# stm8s003f3.net
KiCad netlist of a schematic drawn in Altium Designer
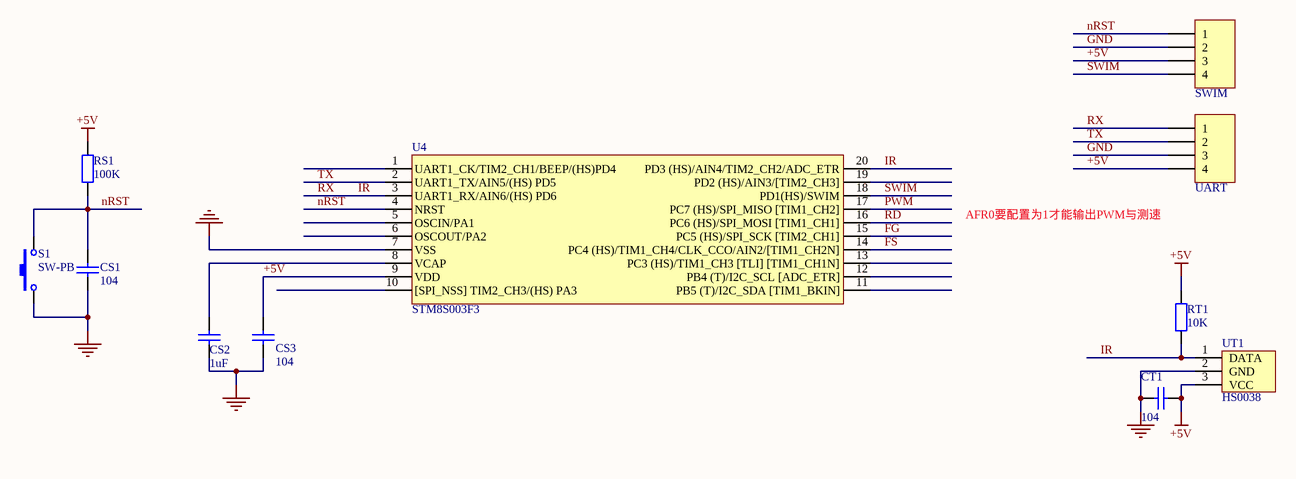
[diagram p0: stm8s003f3.SchDoc]

(export (version "E")
  (design (tool "Eeschema 10.0.6"))
  (components
    (comp (ref "CS1")
      (value "104")
      (footprint "CAPC1608N")
      (description "Capacitor")
      (fields (field (name "Comment") "Cap1") (field (name "PUBLISHER") "Altium Limited"))
      (libsource (lib "Peace的集成库") (part "Cap1"))
    )
    (comp (ref "CS2")
      (value "1uF")
      (footprint "CAPC1608N")
      (description "Capacitor")
      (fields (field (name "Comment") "Cap1") (field (name "PUBLISHER") "Altium Limited"))
      (libsource (lib "Peace的集成库") (part "Cap1"))
    )
    (comp (ref "CS3")
      (value "104")
      (footprint "CAPC1608N")
      (description "Capacitor")
      (fields (field (name "Comment") "Cap1") (field (name "PUBLISHER") "Altium Limited"))
      (libsource (lib "Peace的集成库") (part "Cap1"))
    )
    (comp (ref "CT1")
      (value "104")
      (footprint "CAPC1608N")
      (description "Capacitor")
      (fields (field (name "Comment") "Cap1") (field (name "PUBLISHER") "Altium Limited"))
      (libsource (lib "Peace的集成库") (part "Cap1"))
    )
    (comp (ref "RS1")
      (value "100K")
      (footprint "RESC1608N")
      (description "Resistor")
      (fields (field (name "Comment") "Res1") (field (name "PUBLISHER") "Altium Limited"))
      (libsource (lib "Peace的集成库") (part "Res1"))
    )
    (comp (ref "RT1")
      (value "10K")
      (footprint "RESC1608N")
      (description "Resistor")
      (fields (field (name "Comment") "Res1") (field (name "PUBLISHER") "Altium Limited"))
      (libsource (lib "") (part "Res1_1"))
    )
    (comp (ref "S1")
      (value "SW-PB")
      (footprint "SW-3x6")
      (description "Switch")
      (fields (field (name "PUBLISHER") "Altium Limited"))
      (libsource (lib "Peace的集成库") (part "SW-PB"))
    )
    (comp (ref "SWIM")
      (value "Header 4")
      (footprint "HDR1X4")
      (description "Header, 4-Pin")
      (fields (field (name "PUBLISHER") "Altium Limited"))
      (libsource (lib "Peace的集成库") (part "Header 4"))
    )
    (comp (ref "U4")
      (value "STM8S003F3")
      (footprint "TSSOP20_N")
      (libsource (lib "原理图库") (part "STM8S003F3"))
    )
    (comp (ref "UART")
      (value "Header 4")
      (footprint "HDR1X4")
      (description "Header, 4-Pin")
      (fields (field (name "PUBLISHER") "Altium Limited"))
      (libsource (lib "Peace的集成库") (part "Header 4"))
    )
    (comp (ref "UT1") (value "HS0038") (footprint "HS0038") (libsource (lib "原理图库") (part "HS0038")))
  )
  (nets
    (net (code "1") (name "+5V") (class "Default")
      (node (ref "CS3") (pin "2") (pinfunction "2_2") (pintype "passive"))
      (node (ref "CT1") (pin "1") (pinfunction "1_1") (pintype "passive"))
      (node (ref "RS1") (pin "2") (pinfunction "2_2") (pintype "passive"))
      (node (ref "RT1") (pin "1") (pinfunction "1_1") (pintype "passive"))
      (node (ref "SWIM") (pin "3") (pinfunction "3_3") (pintype "passive"))
      (node (ref "U4") (pin "9") (pinfunction "VDD_9") (pintype "passive"))
      (node (ref "UART") (pin "4") (pinfunction "4_4") (pintype "passive"))
      (node (ref "UT1") (pin "3") (pinfunction "VCC_3") (pintype "passive"))
    )
    (net (code "2") (name "/FG") (class "Default")
      (node (ref "U4") (pin "15") (pinfunction "PC5_(HS)/SPI_SCK_[TIM2_CH1]_15") (pintype "passive"))
    )
    (net (code "3") (name "/FS") (class "Default")
      (node (ref "U4") (pin "14") (pinfunction "PC4_(HS)/TIM1_CH4/CLK_CCO/AIN2/[TIM1_CH2N]_14") (pintype "passive"))
    )
    (net (code "4") (name "/IR") (class "Default")
      (node (ref "RT1") (pin "2") (pinfunction "2_2") (pintype "passive"))
      (node (ref "U4") (pin "20") (pinfunction "PD3_(HS)/AIN4/TIM2_CH2/ADC_ETR_20") (pintype "passive"))
      (node (ref "U4") (pin "3") (pinfunction "UART1_RX/AIN6/(HS)_PD6_3") (pintype "passive"))
      (node (ref "UART") (pin "1") (pinfunction "1_1") (pintype "passive"))
      (node (ref "UT1") (pin "1") (pinfunction "DATA_1") (pintype "passive"))
    )
    (net (code "5") (name "/PWM") (class "Default")
      (node (ref "U4") (pin "17") (pinfunction "PC7_(HS)/SPI_MISO_[TIM1_CH2]_17") (pintype "passive"))
    )
    (net (code "6") (name "/RD") (class "Default")
      (node (ref "U4") (pin "16") (pinfunction "PC6_(HS)/SPI_MOSI_[TIM1_CH1]_16") (pintype "passive"))
    )
    (net (code "7") (name "/SWIM") (class "Default")
      (node (ref "SWIM") (pin "4") (pinfunction "4_4") (pintype "passive"))
      (node (ref "U4") (pin "18") (pinfunction "PD1(HS)/SWIM_18") (pintype "passive"))
    )
    (net (code "8") (name "/TX") (class "Default")
      (node (ref "U4") (pin "2") (pinfunction "UART1_TX/AIN5/(HS)_PD5_2") (pintype "passive"))
      (node (ref "UART") (pin "2") (pinfunction "2_2") (pintype "passive"))
    )
    (net (code "9") (name "/nRST") (class "Default")
      (node (ref "CS1") (pin "2") (pinfunction "2_2") (pintype "passive"))
      (node (ref "RS1") (pin "1") (pinfunction "1_1") (pintype "passive"))
      (node (ref "S1") (pin "2") (pinfunction "2_2") (pintype "passive"))
      (node (ref "SWIM") (pin "1") (pinfunction "1_1") (pintype "passive"))
      (node (ref "U4") (pin "4") (pinfunction "NRST_4") (pintype "passive"))
    )
    (net (code "10") (name "GND") (class "Default")
      (node (ref "CS1") (pin "1") (pinfunction "1_1") (pintype "passive"))
      (node (ref "CS2") (pin "1") (pinfunction "1_1") (pintype "passive"))
      (node (ref "CS3") (pin "1") (pinfunction "1_1") (pintype "passive"))
      (node (ref "CT1") (pin "2") (pinfunction "2_2") (pintype "passive"))
      (node (ref "S1") (pin "1") (pinfunction "1_1") (pintype "passive"))
      (node (ref "SWIM") (pin "2") (pinfunction "2_2") (pintype "passive"))
      (node (ref "U4") (pin "7") (pinfunction "VSS_7") (pintype "passive"))
      (node (ref "UART") (pin "3") (pinfunction "3_3") (pintype "passive"))
      (node (ref "UT1") (pin "2") (pinfunction "GND_2") (pintype "passive"))
    )
    (net (code "11") (name "Net-(U4-VCAP)") (class "Default")
      (node (ref "CS2") (pin "2") (pinfunction "2_2") (pintype "passive"))
      (node (ref "U4") (pin "8") (pinfunction "VCAP_8") (pintype "passive"))
    )
    (net (code "12") (name "unconnected-(U4-OSCIN{slash}PA1-Pad5)") (class "Default")
      (node (ref "U4") (pin "5") (pinfunction "OSCIN/PA1_5") (pintype "passive"))
    )
    (net (code "13") (name "unconnected-(U4-OSCOUT{slash}PA2-Pad6)") (class "Default")
      (node (ref "U4") (pin "6") (pinfunction "OSCOUT/PA2_6") (pintype "passive"))
    )
    (net (code "14") (name "unconnected-(U4-PB4_(T){slash}I2C_SCL_[ADC_ETR]-Pad12)") (class "Default")
      (node (ref "U4") (pin "12") (pinfunction "PB4_(T)/I2C_SCL_[ADC_ETR]_12") (pintype "passive"))
    )
    (net (code "15") (name "unconnected-(U4-PB5_(T){slash}I2C_SDA_[TIM1_BKIN]-Pad11)") (class "Default")
      (node (ref "U4") (pin "11") (pinfunction "PB5_(T)/I2C_SDA_[TIM1_BKIN]_11") (pintype "passive"))
    )
    (net (code "16") (name "unconnected-(U4-PC3_(HS){slash}TIM1_CH3_[TLI]_[TIM1_CH1N]-Pad13)") (class "Default")
      (node (ref "U4") (pin "13") (pinfunction "PC3_(HS)/TIM1_CH3_[TLI]_[TIM1_CH1N]_13") (pintype "passive"))
    )
    (net (code "17") (name "unconnected-(U4-PD2_(HS){slash}AIN3{slash}[TIM2_CH3]-Pad19)") (class "Default")
      (node (ref "U4") (pin "19") (pinfunction "PD2_(HS)/AIN3/[TIM2_CH3]_19") (pintype "passive"))
    )
    (net (code "18") (name "unconnected-(U4-UART1_CK{slash}TIM2_CH1{slash}BEEP{slash}(HS)PD4-Pad1)") (class "Default")
      (node (ref "U4") (pin "1") (pinfunction "UART1_CK/TIM2_CH1/BEEP/(HS)PD4_1") (pintype "passive"))
    )
    (net (code "19") (name "unconnected-(U4-[SPI_NSS]_TIM2_CH3{slash}(HS)_PA3-Pad10)") (class "Default")
      (node (ref "U4") (pin "10") (pinfunction "[SPI_NSS]_TIM2_CH3/(HS)_PA3_10") (pintype "passive"))
    )
  )
)
